# Skematik_Majes.net
KiCad netlist of a schematic drawn in EAGLE
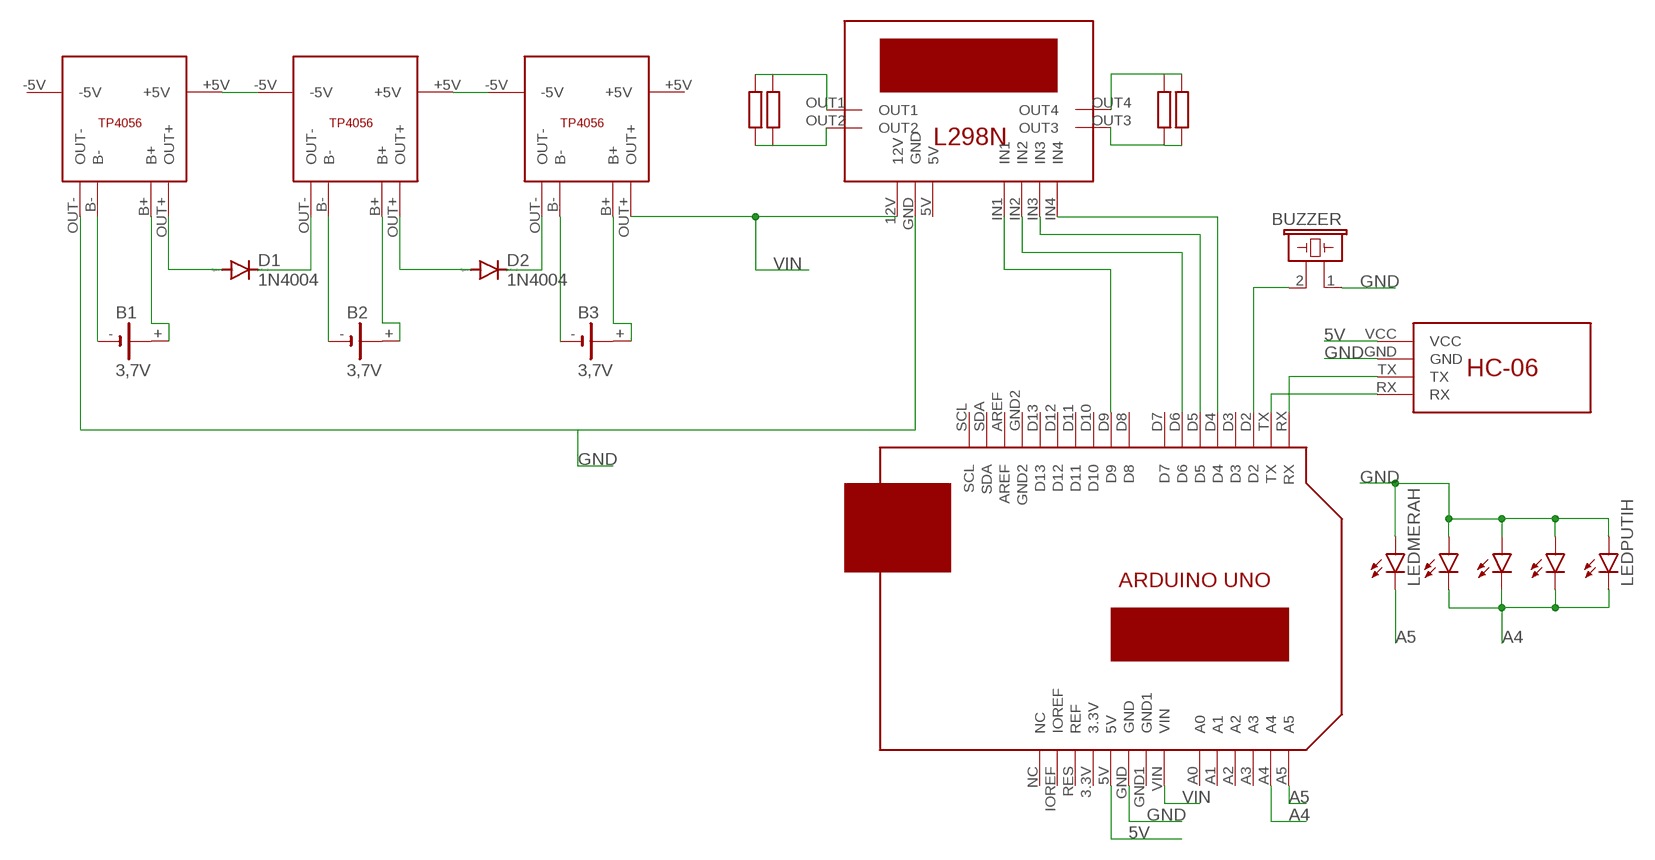
[diagram p0: schematic, sheet 1]

(export (version "E")
  (design (tool "Eeschema 10.0.6"))
  (components
    (comp (ref "B1")
      (value "3,7V")
      (footprint "eagle-import:CRAA")
      (libsource (lib "eagle-import") (part "CRAA"))
    )
    (comp (ref "B2")
      (value "3,7V")
      (footprint "eagle-import:CRAA")
      (libsource (lib "eagle-import") (part "CRAA"))
    )
    (comp (ref "B3")
      (value "3,7V")
      (footprint "eagle-import:CRAA")
      (libsource (lib "eagle-import") (part "CRAA"))
    )
    (comp (ref "BUZZER")
      (value "B/C11L")
      (footprint "eagle-import:B_C11L")
      (libsource (lib "eagle-import") (part "B/C11L"))
    )
    (comp (ref "D1")
      (value "1N4004")
      (footprint "eagle-import:DO41-10")
      (libsource (lib "eagle-import") (part "1N4004"))
    )
    (comp (ref "D2")
      (value "1N4004")
      (footprint "eagle-import:DO41-10")
      (libsource (lib "eagle-import") (part "1N4004"))
    )
    (comp (ref "LED1")
      (value "LAW57B")
      (footprint "eagle-import:W57B")
      (libsource (lib "eagle-import") (part "W57BLA"))
    )
    (comp (ref "LED2")
      (value "LAW57B")
      (footprint "eagle-import:W57B")
      (libsource (lib "eagle-import") (part "W57BLA"))
    )
    (comp (ref "LED3")
      (value "LAW57B")
      (footprint "eagle-import:W57B")
      (libsource (lib "eagle-import") (part "W57BLA"))
    )
    (comp (ref "LEDMERAH")
      (value "LAW57B")
      (footprint "eagle-import:W57B")
      (libsource (lib "eagle-import") (part "W57BLA"))
    )
    (comp (ref "LEDPUTIH")
      (value "LAW57B")
      (footprint "eagle-import:W57B")
      (libsource (lib "eagle-import") (part "W57BLA"))
    )
    (comp (ref "U$1")
      (value "ARDUINOUNO")
      (footprint "eagle-import:ARDUINOUNO")
      (libsource (lib "eagle-import") (part "ARDUINOUNO"))
    )
    (comp (ref "U$2")
      (value "HC-06")
      (footprint "eagle-import:HC-06")
      (libsource (lib "eagle-import") (part "HC-06"))
    )
    (comp (ref "U$3")
      (value "L298N")
      (footprint "eagle-import:L298N")
      (libsource (lib "eagle-import") (part "L298N"))
    )
    (comp (ref "U$4")
      (value "TP4086")
      (footprint "eagle-import:TP4056")
      (libsource (lib "eagle-import") (part "TP4086"))
    )
    (comp (ref "U$5")
      (value "TP4086")
      (footprint "eagle-import:TP4056")
      (libsource (lib "eagle-import") (part "TP4086"))
    )
    (comp (ref "U$6")
      (value "TP4086")
      (footprint "eagle-import:TP4056")
      (libsource (lib "eagle-import") (part "TP4086"))
    )
  )
  (nets
    (net (code "1") (name "/5V") (class "Default")
      (node (ref "U$1") (pin "5V") (pinfunction "5V_5V") (pintype "bidirectional"))
      (node (ref "U$2") (pin "VCC") (pinfunction "VCC_VCC") (pintype "bidirectional"))
    )
    (net (code "2") (name "/A4") (class "Default")
      (node (ref "LED1") (pin "C") (pinfunction "C_C") (pintype "passive"))
      (node (ref "LED1") (pin "C@1") (pinfunction "C_C@1") (pintype "passive"))
      (node (ref "LED1") (pin "C@2") (pinfunction "C_C@2") (pintype "passive"))
      (node (ref "LED1") (pin "C@3") (pinfunction "C_C@3") (pintype "passive"))
      (node (ref "LED1") (pin "C@4") (pinfunction "C_C@4") (pintype "passive"))
      (node (ref "LED1") (pin "C@5") (pinfunction "C_C@5") (pintype "passive"))
      (node (ref "LED2") (pin "C") (pinfunction "C_C") (pintype "passive"))
      (node (ref "LED2") (pin "C@1") (pinfunction "C_C@1") (pintype "passive"))
      (node (ref "LED2") (pin "C@2") (pinfunction "C_C@2") (pintype "passive"))
      (node (ref "LED2") (pin "C@3") (pinfunction "C_C@3") (pintype "passive"))
      (node (ref "LED2") (pin "C@4") (pinfunction "C_C@4") (pintype "passive"))
      (node (ref "LED2") (pin "C@5") (pinfunction "C_C@5") (pintype "passive"))
      (node (ref "LED3") (pin "C") (pinfunction "C_C") (pintype "passive"))
      (node (ref "LED3") (pin "C@1") (pinfunction "C_C@1") (pintype "passive"))
      (node (ref "LED3") (pin "C@2") (pinfunction "C_C@2") (pintype "passive"))
      (node (ref "LED3") (pin "C@3") (pinfunction "C_C@3") (pintype "passive"))
      (node (ref "LED3") (pin "C@4") (pinfunction "C_C@4") (pintype "passive"))
      (node (ref "LED3") (pin "C@5") (pinfunction "C_C@5") (pintype "passive"))
      (node (ref "LEDPUTIH") (pin "C") (pinfunction "C_C") (pintype "passive"))
      (node (ref "LEDPUTIH") (pin "C@1") (pinfunction "C_C@1") (pintype "passive"))
      (node (ref "LEDPUTIH") (pin "C@2") (pinfunction "C_C@2") (pintype "passive"))
      (node (ref "LEDPUTIH") (pin "C@3") (pinfunction "C_C@3") (pintype "passive"))
      (node (ref "LEDPUTIH") (pin "C@4") (pinfunction "C_C@4") (pintype "passive"))
      (node (ref "LEDPUTIH") (pin "C@5") (pinfunction "C_C@5") (pintype "passive"))
      (node (ref "U$1") (pin "A4") (pinfunction "A4_A4") (pintype "bidirectional"))
    )
    (net (code "3") (name "/A5") (class "Default")
      (node (ref "LEDMERAH") (pin "C") (pinfunction "C_C") (pintype "passive"))
      (node (ref "LEDMERAH") (pin "C@1") (pinfunction "C_C@1") (pintype "passive"))
      (node (ref "LEDMERAH") (pin "C@2") (pinfunction "C_C@2") (pintype "passive"))
      (node (ref "LEDMERAH") (pin "C@3") (pinfunction "C_C@3") (pintype "passive"))
      (node (ref "LEDMERAH") (pin "C@4") (pinfunction "C_C@4") (pintype "passive"))
      (node (ref "LEDMERAH") (pin "C@5") (pinfunction "C_C@5") (pintype "passive"))
      (node (ref "U$1") (pin "A5") (pinfunction "A5_A5") (pintype "bidirectional"))
    )
    (net (code "4") (name "/GND") (class "Default")
      (node (ref "BUZZER") (pin "1") (pinfunction "1_1") (pintype "passive"))
      (node (ref "LED1") (pin "A") (pinfunction "A_A") (pintype "passive"))
      (node (ref "LED2") (pin "A") (pinfunction "A_A") (pintype "passive"))
      (node (ref "LED3") (pin "A") (pinfunction "A_A") (pintype "passive"))
      (node (ref "LEDMERAH") (pin "A") (pinfunction "A_A") (pintype "passive"))
      (node (ref "LEDPUTIH") (pin "A") (pinfunction "A_A") (pintype "passive"))
      (node (ref "U$1") (pin "GND") (pinfunction "GND_GND") (pintype "bidirectional"))
      (node (ref "U$2") (pin "GND") (pinfunction "GND_GND") (pintype "bidirectional"))
      (node (ref "U$3") (pin "GND") (pinfunction "GND_GND") (pintype "bidirectional"))
      (node (ref "U$4") (pin "OUT-") (pinfunction "OUT-_OUT-") (pintype "bidirectional"))
    )
    (net (code "5") (name "/VIN") (class "Default")
      (node (ref "U$1") (pin "VIN") (pinfunction "VIN_VIN") (pintype "bidirectional"))
      (node (ref "U$3") (pin "12V") (pinfunction "12V_12V") (pintype "bidirectional"))
      (node (ref "U$6") (pin "OUT+") (pinfunction "OUT+_OUT+") (pintype "bidirectional"))
    )
    (net (code "6") (name "Net-(B1-Pad+)") (class "Default")
      (node (ref "B1") (pin "+") (pinfunction "+_+") (pintype "passive"))
      (node (ref "U$4") (pin "B+") (pinfunction "B+_B+") (pintype "bidirectional"))
    )
    (net (code "7") (name "Net-(B1-Pad-)") (class "Default")
      (node (ref "B1") (pin "-") (pinfunction "-_-") (pintype "passive"))
      (node (ref "U$4") (pin "B-") (pinfunction "B-_B-") (pintype "bidirectional"))
    )
    (net (code "8") (name "Net-(B2-Pad+)") (class "Default")
      (node (ref "B2") (pin "+") (pinfunction "+_+") (pintype "passive"))
      (node (ref "U$5") (pin "B+") (pinfunction "B+_B+") (pintype "bidirectional"))
    )
    (net (code "9") (name "Net-(B2-Pad-)") (class "Default")
      (node (ref "B2") (pin "-") (pinfunction "-_-") (pintype "passive"))
      (node (ref "U$5") (pin "B-") (pinfunction "B-_B-") (pintype "bidirectional"))
    )
    (net (code "10") (name "Net-(B3-Pad+)") (class "Default")
      (node (ref "B3") (pin "+") (pinfunction "+_+") (pintype "passive"))
      (node (ref "U$6") (pin "B+") (pinfunction "B+_B+") (pintype "bidirectional"))
    )
    (net (code "11") (name "Net-(B3-Pad-)") (class "Default")
      (node (ref "B3") (pin "-") (pinfunction "-_-") (pintype "passive"))
      (node (ref "U$6") (pin "B-") (pinfunction "B-_B-") (pintype "bidirectional"))
    )
    (net (code "12") (name "Net-(BUZZER-Pad2)") (class "Default")
      (node (ref "BUZZER") (pin "2") (pinfunction "2_2") (pintype "passive"))
      (node (ref "U$1") (pin "D2") (pinfunction "D2_D2") (pintype "bidirectional"))
    )
    (net (code "13") (name "Net-(D1-PadA)") (class "Default")
      (node (ref "D1") (pin "A") (pinfunction "A_A") (pintype "passive"))
      (node (ref "U$4") (pin "OUT+") (pinfunction "OUT+_OUT+") (pintype "bidirectional"))
    )
    (net (code "14") (name "Net-(D1-PadC)") (class "Default")
      (node (ref "D1") (pin "C") (pinfunction "C_C") (pintype "passive"))
      (node (ref "U$5") (pin "OUT-") (pinfunction "OUT-_OUT-") (pintype "bidirectional"))
    )
    (net (code "15") (name "Net-(D2-PadA)") (class "Default")
      (node (ref "D2") (pin "A") (pinfunction "A_A") (pintype "passive"))
      (node (ref "U$5") (pin "OUT+") (pinfunction "OUT+_OUT+") (pintype "bidirectional"))
    )
    (net (code "16") (name "Net-(D2-PadC)") (class "Default")
      (node (ref "D2") (pin "C") (pinfunction "C_C") (pintype "passive"))
      (node (ref "U$6") (pin "OUT-") (pinfunction "OUT-_OUT-") (pintype "bidirectional"))
    )
    (net (code "17") (name "Net-(U$1-PadD4)") (class "Default")
      (node (ref "U$1") (pin "D4") (pinfunction "D4_D4") (pintype "bidirectional"))
      (node (ref "U$3") (pin "IN4") (pinfunction "IN4_IN4") (pintype "bidirectional"))
    )
    (net (code "18") (name "Net-(U$1-PadD5)") (class "Default")
      (node (ref "U$1") (pin "D5") (pinfunction "D5_D5") (pintype "bidirectional"))
      (node (ref "U$3") (pin "IN3") (pinfunction "IN3_IN3") (pintype "bidirectional"))
    )
    (net (code "19") (name "Net-(U$1-PadD6)") (class "Default")
      (node (ref "U$1") (pin "D6") (pinfunction "D6_D6") (pintype "bidirectional"))
      (node (ref "U$3") (pin "IN2") (pinfunction "IN2_IN2") (pintype "bidirectional"))
    )
    (net (code "20") (name "Net-(U$1-PadD9)") (class "Default")
      (node (ref "U$1") (pin "D9") (pinfunction "D9_D9") (pintype "bidirectional"))
      (node (ref "U$3") (pin "IN1") (pinfunction "IN1_IN1") (pintype "bidirectional"))
    )
    (net (code "21") (name "Net-(U$1-PadRX)") (class "Default")
      (node (ref "U$1") (pin "RX") (pinfunction "RX_RX") (pintype "bidirectional"))
      (node (ref "U$2") (pin "TX") (pinfunction "TX_TX") (pintype "bidirectional"))
    )
    (net (code "22") (name "Net-(U$1-PadTX)") (class "Default")
      (node (ref "U$1") (pin "TX") (pinfunction "TX_TX") (pintype "bidirectional"))
      (node (ref "U$2") (pin "RX") (pinfunction "RX_RX") (pintype "bidirectional"))
    )
    (net (code "23") (name "Net-(U$4-Pad+5V)") (class "Default")
      (node (ref "U$4") (pin "+5V") (pinfunction "+5V_+5V") (pintype "bidirectional"))
      (node (ref "U$5") (pin "-5V") (pinfunction "-5V_-5V") (pintype "bidirectional"))
    )
    (net (code "24") (name "Net-(U$5-Pad+5V)") (class "Default")
      (node (ref "U$5") (pin "+5V") (pinfunction "+5V_+5V") (pintype "bidirectional"))
      (node (ref "U$6") (pin "-5V") (pinfunction "-5V_-5V") (pintype "bidirectional"))
    )
    (net (code "25") (name "unconnected-(B1-+-Pad+@1)") (class "Default")
      (node (ref "B1") (pin "+@1") (pinfunction "+_+@1") (pintype "passive"))
    )
    (net (code "26") (name "unconnected-(B2-+-Pad+@1)") (class "Default")
      (node (ref "B2") (pin "+@1") (pinfunction "+_+@1") (pintype "passive"))
    )
    (net (code "27") (name "unconnected-(B3-+-Pad+@1)") (class "Default")
      (node (ref "B3") (pin "+@1") (pinfunction "+_+@1") (pintype "passive"))
    )
    (net (code "28") (name "unconnected-(U$1-Pad3.3V)") (class "Default")
      (node (ref "U$1") (pin "3.3V") (pinfunction "3.3V_3.3V") (pintype "bidirectional"))
    )
    (net (code "29") (name "unconnected-(U$1-PadA0)") (class "Default")
      (node (ref "U$1") (pin "A0") (pinfunction "A0_A0") (pintype "bidirectional"))
    )
    (net (code "30") (name "unconnected-(U$1-PadA1)") (class "Default")
      (node (ref "U$1") (pin "A1") (pinfunction "A1_A1") (pintype "bidirectional"))
    )
    (net (code "31") (name "unconnected-(U$1-PadA2)") (class "Default")
      (node (ref "U$1") (pin "A2") (pinfunction "A2_A2") (pintype "bidirectional"))
    )
    (net (code "32") (name "unconnected-(U$1-PadA3)") (class "Default")
      (node (ref "U$1") (pin "A3") (pinfunction "A3_A3") (pintype "bidirectional"))
    )
    (net (code "33") (name "unconnected-(U$1-PadAREF)") (class "Default")
      (node (ref "U$1") (pin "AREF") (pinfunction "AREF_AREF") (pintype "bidirectional"))
    )
    (net (code "34") (name "unconnected-(U$1-PadD3)") (class "Default")
      (node (ref "U$1") (pin "D3") (pinfunction "D3_D3") (pintype "bidirectional"))
    )
    (net (code "35") (name "unconnected-(U$1-PadD7)") (class "Default")
      (node (ref "U$1") (pin "D7") (pinfunction "D7_D7") (pintype "bidirectional"))
    )
    (net (code "36") (name "unconnected-(U$1-PadD8)") (class "Default")
      (node (ref "U$1") (pin "D8") (pinfunction "D8_D8") (pintype "bidirectional"))
    )
    (net (code "37") (name "unconnected-(U$1-PadD10)") (class "Default")
      (node (ref "U$1") (pin "D10") (pinfunction "D10_D10") (pintype "bidirectional"))
    )
    (net (code "38") (name "unconnected-(U$1-PadD11)") (class "Default")
      (node (ref "U$1") (pin "D11") (pinfunction "D11_D11") (pintype "bidirectional"))
    )
    (net (code "39") (name "unconnected-(U$1-PadD12)") (class "Default")
      (node (ref "U$1") (pin "D12") (pinfunction "D12_D12") (pintype "bidirectional"))
    )
    (net (code "40") (name "unconnected-(U$1-PadD13)") (class "Default")
      (node (ref "U$1") (pin "D13") (pinfunction "D13_D13") (pintype "bidirectional"))
    )
    (net (code "41") (name "unconnected-(U$1-PadGND1)") (class "Default")
      (node (ref "U$1") (pin "GND1") (pinfunction "GND1_GND1") (pintype "bidirectional"))
    )
    (net (code "42") (name "unconnected-(U$1-PadGND2)") (class "Default")
      (node (ref "U$1") (pin "GND2") (pinfunction "GND2_GND2") (pintype "bidirectional"))
    )
    (net (code "43") (name "unconnected-(U$1-PadIOREF)") (class "Default")
      (node (ref "U$1") (pin "IOREF") (pinfunction "IOREF_IOREF") (pintype "bidirectional"))
    )
    (net (code "44") (name "unconnected-(U$1-PadNC)") (class "Default")
      (node (ref "U$1") (pin "NC") (pinfunction "NC_NC") (pintype "bidirectional"))
    )
    (net (code "45") (name "unconnected-(U$1-PadSCL)") (class "Default")
      (node (ref "U$1") (pin "SCL") (pinfunction "SCL_SCL") (pintype "bidirectional"))
    )
    (net (code "46") (name "unconnected-(U$1-PadSDA)") (class "Default")
      (node (ref "U$1") (pin "SDA") (pinfunction "SDA_SDA") (pintype "bidirectional"))
    )
    (net (code "47") (name "unconnected-(U$1-REF-PadRES)") (class "Default")
      (node (ref "U$1") (pin "RES") (pinfunction "REF_RES") (pintype "bidirectional"))
    )
    (net (code "48") (name "unconnected-(U$3-Pad5V)") (class "Default")
      (node (ref "U$3") (pin "5V") (pinfunction "5V_5V") (pintype "bidirectional"))
    )
    (net (code "49") (name "unconnected-(U$3-PadOUT1)") (class "Default")
      (node (ref "U$3") (pin "OUT1") (pinfunction "OUT1_OUT1") (pintype "bidirectional"))
    )
    (net (code "50") (name "unconnected-(U$3-PadOUT2)") (class "Default")
      (node (ref "U$3") (pin "OUT2") (pinfunction "OUT2_OUT2") (pintype "bidirectional"))
    )
    (net (code "51") (name "unconnected-(U$3-PadOUT3)") (class "Default")
      (node (ref "U$3") (pin "OUT3") (pinfunction "OUT3_OUT3") (pintype "bidirectional"))
    )
    (net (code "52") (name "unconnected-(U$3-PadOUT4)") (class "Default")
      (node (ref "U$3") (pin "OUT4") (pinfunction "OUT4_OUT4") (pintype "bidirectional"))
    )
    (net (code "53") (name "unconnected-(U$4-Pad-5V)") (class "Default")
      (node (ref "U$4") (pin "-5V") (pinfunction "-5V_-5V") (pintype "bidirectional"))
    )
    (net (code "54") (name "unconnected-(U$6-Pad+5V)") (class "Default")
      (node (ref "U$6") (pin "+5V") (pinfunction "+5V_+5V") (pintype "bidirectional"))
    )
  )
)
